# AD9864.net
KiCad netlist of a schematic drawn in Altium Designer
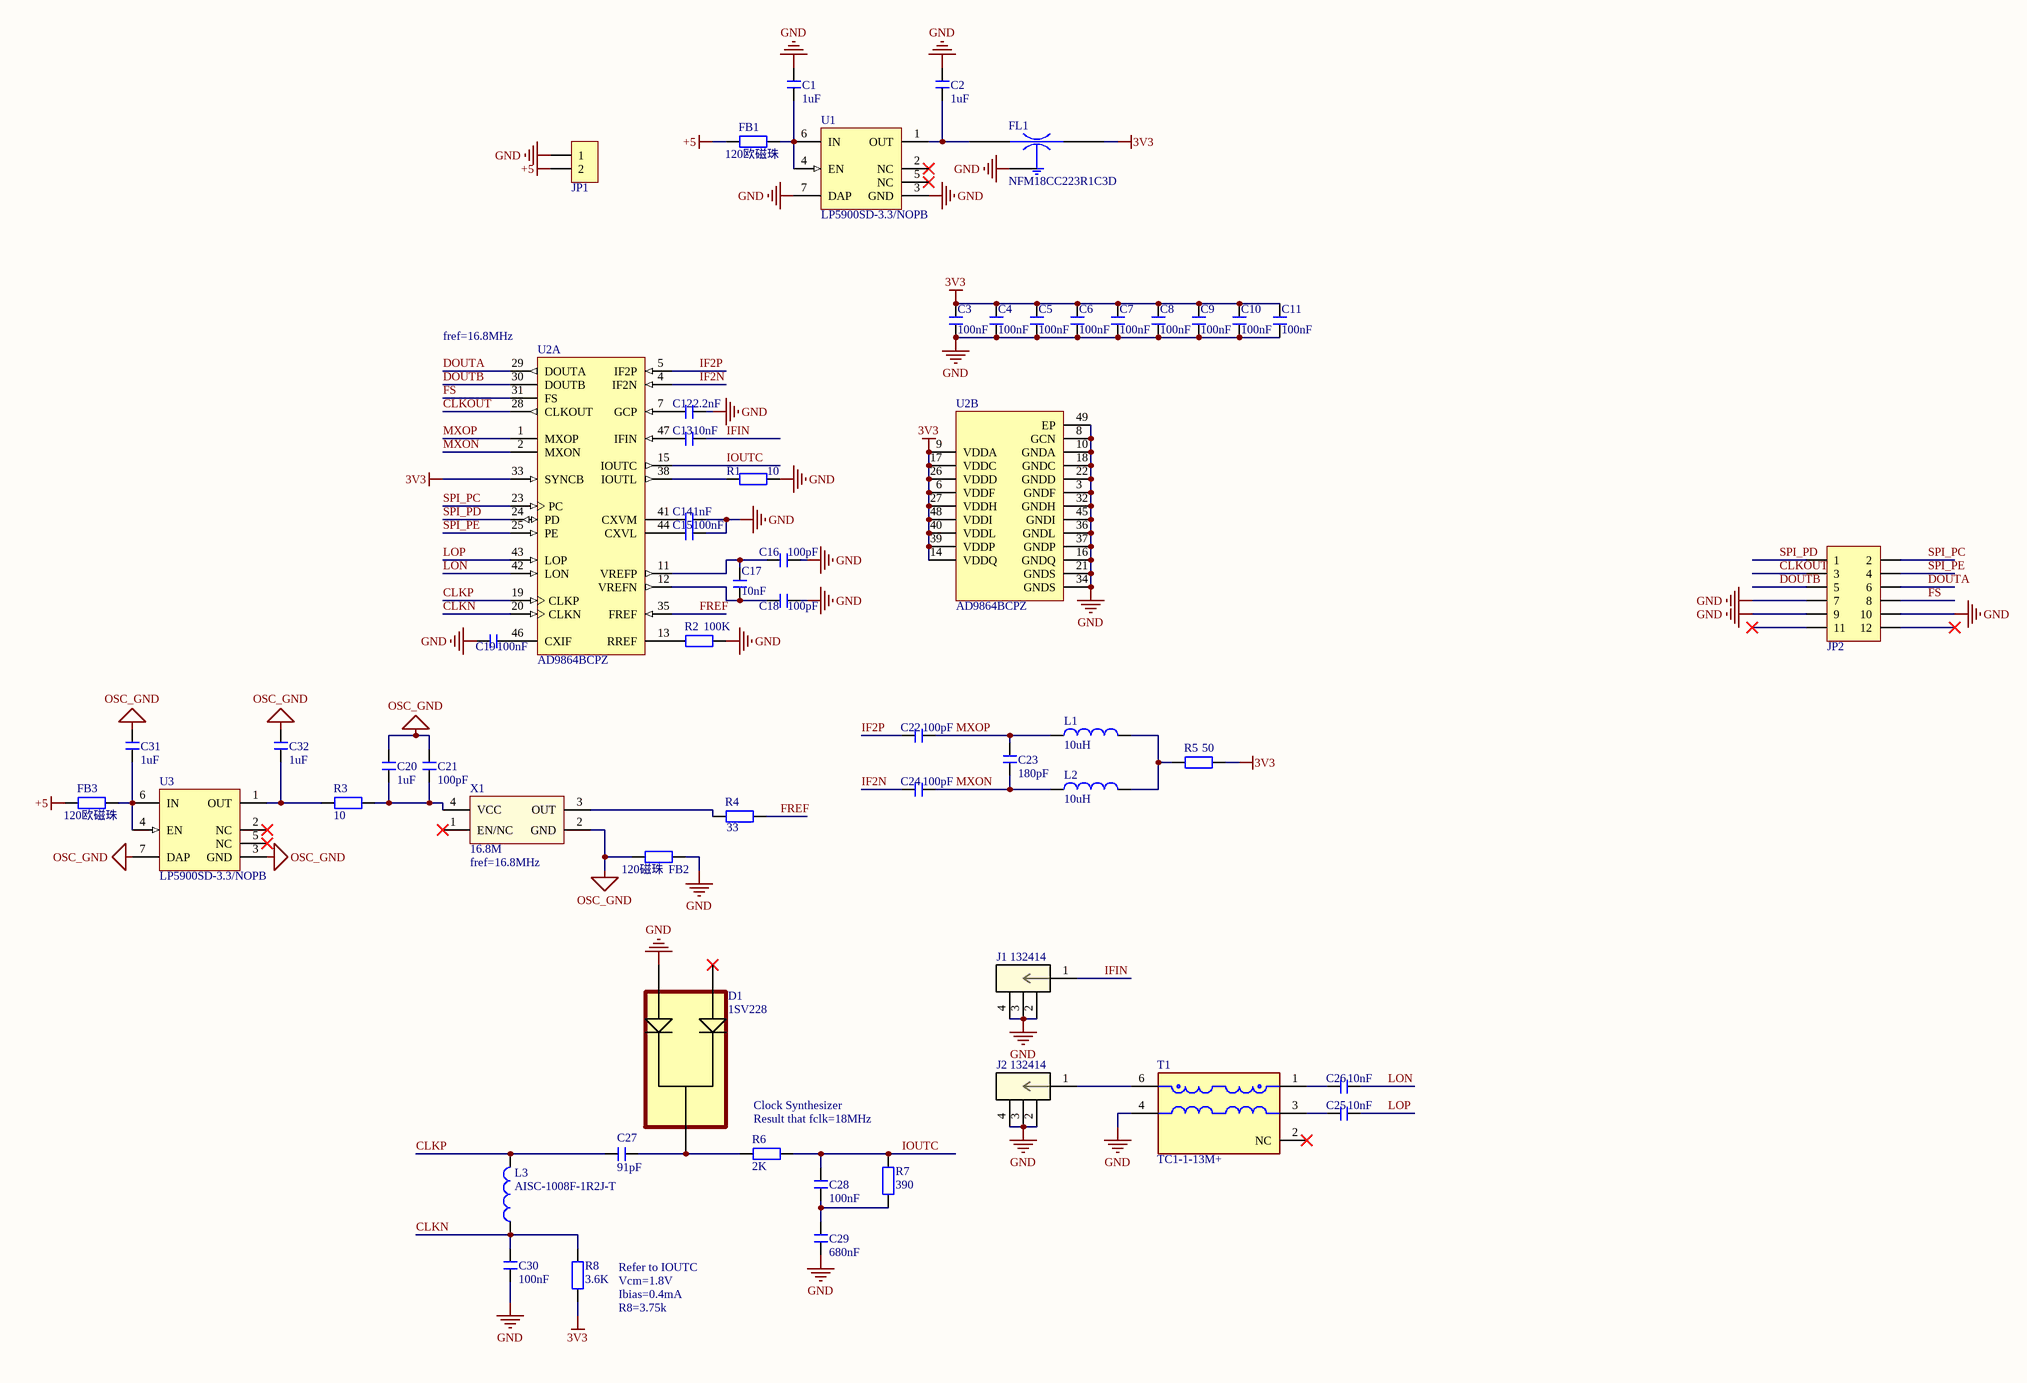
[diagram p0: AD9864.SchDoc]

(export (version "E")
  (design (tool "Eeschema 10.0.6"))
  (components
    (comp (ref "C1")
      (value "1uF")
      (footprint "C 0603_L")
      (description "贴片电容")
      (libsource (lib "01 - 电容-电阻-电感") (part "C"))
    )
    (comp (ref "C2")
      (value "1uF")
      (footprint "C 0603_L")
      (description "贴片电容")
      (libsource (lib "01 - 电容-电阻-电感") (part "C"))
    )
    (comp (ref "C3")
      (value "100nF")
      (footprint "C 0402_L")
      (description "贴片电容")
      (libsource (lib "01 - 电容-电阻-电感") (part "C"))
    )
    (comp (ref "C4")
      (value "100nF")
      (footprint "C 0402_L")
      (description "贴片电容")
      (libsource (lib "01 - 电容-电阻-电感") (part "C"))
    )
    (comp (ref "C5")
      (value "100nF")
      (footprint "C 0402_L")
      (description "贴片电容")
      (libsource (lib "01 - 电容-电阻-电感") (part "C"))
    )
    (comp (ref "C6")
      (value "100nF")
      (footprint "C 0402_L")
      (description "贴片电容")
      (libsource (lib "01 - 电容-电阻-电感") (part "C"))
    )
    (comp (ref "C7")
      (value "100nF")
      (footprint "C 0402_L")
      (description "贴片电容")
      (libsource (lib "01 - 电容-电阻-电感") (part "C"))
    )
    (comp (ref "C8")
      (value "100nF")
      (footprint "C 0402_L")
      (description "贴片电容")
      (libsource (lib "01 - 电容-电阻-电感") (part "C"))
    )
    (comp (ref "C9")
      (value "100nF")
      (footprint "C 0402_L")
      (description "贴片电容")
      (libsource (lib "01 - 电容-电阻-电感") (part "C"))
    )
    (comp (ref "C10")
      (value "100nF")
      (footprint "C 0402_L")
      (description "贴片电容")
      (libsource (lib "01 - 电容-电阻-电感") (part "C"))
    )
    (comp (ref "C11")
      (value "100nF")
      (footprint "C 0402_L")
      (description "贴片电容")
      (libsource (lib "01 - 电容-电阻-电感") (part "C"))
    )
    (comp (ref "C12")
      (value "2.2nF")
      (footprint "C 0402_L")
      (description "贴片电容")
      (libsource (lib "01 - 电容-电阻-电感") (part "C"))
    )
    (comp (ref "C13")
      (value "10nF")
      (footprint "C 0402_L")
      (description "贴片电容")
      (libsource (lib "01 - 电容-电阻-电感") (part "C"))
    )
    (comp (ref "C14")
      (value "1nF")
      (footprint "C 0402_L")
      (description "贴片电容")
      (libsource (lib "01 - 电容-电阻-电感") (part "C"))
    )
    (comp (ref "C15")
      (value "100nF")
      (footprint "C 0402_L")
      (description "贴片电容")
      (libsource (lib "01 - 电容-电阻-电感") (part "C"))
    )
    (comp (ref "C16")
      (value "100pF")
      (footprint "C 0402_L")
      (description "贴片电容")
      (libsource (lib "01 - 电容-电阻-电感") (part "C"))
    )
    (comp (ref "C17")
      (value "10nF")
      (footprint "C 0402_L")
      (description "贴片电容")
      (libsource (lib "01 - 电容-电阻-电感") (part "C"))
    )
    (comp (ref "C18")
      (value "100pF")
      (footprint "C 0402_L")
      (description "贴片电容")
      (libsource (lib "01 - 电容-电阻-电感") (part "C"))
    )
    (comp (ref "C19")
      (value "100nF")
      (footprint "C 0402_L")
      (description "贴片电容")
      (libsource (lib "01 - 电容-电阻-电感") (part "C"))
    )
    (comp (ref "C20")
      (value "1uF")
      (footprint "C 0603_L")
      (description "贴片电容")
      (libsource (lib "01 - 电容-电阻-电感") (part "C"))
    )
    (comp (ref "C21")
      (value "100pF")
      (footprint "C 0603_L")
      (description "贴片电容")
      (libsource (lib "01 - 电容-电阻-电感") (part "C"))
    )
    (comp (ref "C22")
      (value "100pF")
      (footprint "C 0402_L")
      (description "贴片电容")
      (libsource (lib "01 - 电容-电阻-电感") (part "C"))
    )
    (comp (ref "C23")
      (value "180pF")
      (footprint "C 0402_L")
      (description "贴片电容")
      (libsource (lib "01 - 电容-电阻-电感") (part "C"))
    )
    (comp (ref "C24")
      (value "100pF")
      (footprint "C 0402_L")
      (description "贴片电容")
      (libsource (lib "01 - 电容-电阻-电感") (part "C"))
    )
    (comp (ref "C25")
      (value "10nF")
      (footprint "C 0402_L")
      (description "贴片电容")
      (libsource (lib "01 - 电容-电阻-电感") (part "C"))
    )
    (comp (ref "C26")
      (value "10nF")
      (footprint "C 0402_L")
      (description "贴片电容")
      (libsource (lib "01 - 电容-电阻-电感") (part "C"))
    )
    (comp (ref "C27")
      (value "91pF")
      (footprint "C 0402_L")
      (description "贴片电容")
      (libsource (lib "01 - 电容-电阻-电感") (part "C"))
    )
    (comp (ref "C28")
      (value "100nF")
      (footprint "C 0402_L")
      (description "贴片电容")
      (libsource (lib "01 - 电容-电阻-电感") (part "C"))
    )
    (comp (ref "C29")
      (value "680nF")
      (footprint "C 0402_L")
      (description "贴片电容")
      (libsource (lib "01 - 电容-电阻-电感") (part "C"))
    )
    (comp (ref "C30")
      (value "100nF")
      (footprint "C 0402_L")
      (description "贴片电容")
      (libsource (lib "01 - 电容-电阻-电感") (part "C"))
    )
    (comp (ref "C31")
      (value "1uF")
      (footprint "C 0603_L")
      (description "贴片电容")
      (libsource (lib "01 - 电容-电阻-电感") (part "C"))
    )
    (comp (ref "C32")
      (value "1uF")
      (footprint "C 0603_L")
      (description "贴片电容")
      (libsource (lib "01 - 电容-电阻-电感") (part "C"))
    )
    (comp (ref "D1")
      (value "1SV228")
      (footprint "TRANS_SSM3J325F,LF")
      (description "Varactor 1 Pair Common Cathode 15V Surface Mount S-Mini")
      (fields (field (name "MF") "Toshiba"))
      (libsource (lib "1SV228") (part "1SV228"))
    )
    (comp (ref "FB1")
      (value "120欧磁珠")
      (footprint "R 0603_L")
      (description "贴片电阻")
      (libsource (lib "01 - 电容-电阻-电感") (part "R"))
    )
    (comp (ref "FB2")
      (value "120磁珠")
      (footprint "R 0603_L")
      (description "贴片电阻")
      (libsource (lib "01 - 电容-电阻-电感") (part "R"))
    )
    (comp (ref "FB3")
      (value "120欧磁珠")
      (footprint "R 0603_L")
      (description "贴片电阻")
      (libsource (lib "01 - 电容-电阻-电感") (part "R"))
    )
    (comp (ref "FL1")
      (value "NFM18CC223R1C3D")
      (footprint "FIL_NFM18CC223R1C3D")
      (description "SMD Capacitor with Capacitance: 22000pF Tol. 20%. Rated Voltage: 16Vdc")
      (fields (field (name "MF") "Murata"))
      (libsource (lib "NFM18CC223R1C3D") (part "NFM18CC223R1C3D"))
    )
    (comp (ref "J1")
      (value "132414")
      (footprint "CONN_132414_AMP")
      (description "No Description Available")
      (fields (field (name "COPYRIGHT") "Copyright (C) 2022 Ultra Librarian. All rights reserved."))
      (libsource (lib "细针大偏脚SMA(用这个)") (part "132414"))
    )
    (comp (ref "J2")
      (value "132414")
      (footprint "CONN_132414_AMP")
      (description "No Description Available")
      (fields (field (name "COPYRIGHT") "Copyright (C) 2022 Ultra Librarian. All rights reserved."))
      (libsource (lib "细针大偏脚SMA(用这个)") (part "132414"))
    )
    (comp (ref "JP1")
      (value "HDR-1X2")
      (footprint "KF2510-LI-2P")
      (description "2P接插件")
      (libsource (lib "18 - 接插件-脚距2.54mm (100mil) ") (part "Header 2"))
    )
    (comp (ref "JP2")
      (value "Header 6X2")
      (footprint "HDR2.54-WI-2x6P")
      (description "6*2P接插件")
      (libsource (lib "18 - 接插件-脚距2.54mm (100mil) ") (part "Header  6X2"))
    )
    (comp (ref "L1")
      (value "10uH")
      (footprint "L 0603")
      (description "小功率贴片电感")
      (libsource (lib "01 - 电容-电阻-电感") (part "L"))
    )
    (comp (ref "L2")
      (value "10uH")
      (footprint "L 0603")
      (description "小功率贴片电感")
      (libsource (lib "01 - 电容-电阻-电感") (part "L"))
    )
    (comp (ref "L3")
      (value "AISC-1008F-1R2J-T")
      (footprint "IND-SMD_L2.9-W2.8")
      (description "小功率贴片电感")
      (libsource (lib "01 - 电容-电阻-电感") (part "L"))
    )
    (comp (ref "R1")
      (value "10")
      (footprint "R 0402_L")
      (description "贴片电阻")
      (libsource (lib "01 - 电容-电阻-电感") (part "R"))
    )
    (comp (ref "R2")
      (value "100K")
      (footprint "R 0402_L")
      (description "贴片电阻")
      (libsource (lib "01 - 电容-电阻-电感") (part "R"))
    )
    (comp (ref "R3")
      (value "10")
      (footprint "R 0603_L")
      (description "贴片电阻")
      (libsource (lib "01 - 电容-电阻-电感") (part "R"))
    )
    (comp (ref "R4")
      (value "33")
      (footprint "R 0603_L")
      (description "贴片电阻")
      (libsource (lib "01 - 电容-电阻-电感") (part "R"))
    )
    (comp (ref "R5")
      (value "50")
      (footprint "R 0402_L")
      (description "贴片电阻")
      (libsource (lib "01 - 电容-电阻-电感") (part "R"))
    )
    (comp (ref "R6")
      (value "2K")
      (footprint "R 0402_L")
      (description "贴片电阻")
      (libsource (lib "01 - 电容-电阻-电感") (part "R"))
    )
    (comp (ref "R7")
      (value "390")
      (footprint "R 0402_L")
      (description "贴片电阻")
      (libsource (lib "01 - 电容-电阻-电感") (part "R"))
    )
    (comp (ref "R8")
      (value "3.6K")
      (footprint "R 0603_L")
      (description "贴片电阻")
      (libsource (lib "01 - 电容-电阻-电感") (part "R"))
    )
    (comp (ref "T1")
      (value "TC1-1-13M+")
      (footprint "FP-TC1-1-13M+-MFG")
      (description "RF Transformer 1: 1 5 Terminal SMD")
      (libsource (lib "DigiPCBA Workspace") (part "bfcd2037c1656edfb93934ecf7289be"))
    )
    (comp (ref "U1")
      (value "LP5900SD-3.3/NOPB")
      (footprint "NGF0006A_V")
      (description "150-mA, low-noise, low-IQ, low-dropout voltage regulator with enable 6-WSON -40 to 125")
      (libsource (lib "DigiPCBA Workspace") (part "PM-REG-LP5900-IL7"))
    )
    (comp (ref "U2")
      (value "AD9864BCPZ")
      (footprint "CP-48-1_M")
      (description "IC IF SUBSYSTEM GEN-PURP 48LFCSP")
      (libsource (lib "DigiPCBA Workspace") (part "ADI-AD9864-CP-48-1"))
    )
    (comp (ref "U3")
      (value "LP5900SD-3.3/NOPB")
      (footprint "NGF0006A_V")
      (description "150-mA, low-noise, low-IQ, low-dropout voltage regulator with enable 6-WSON -40 to 125")
      (libsource (lib "DigiPCBA Workspace") (part "PM-REG-LP5900-IL7"))
    )
    (comp (ref "X1")
      (value "16.8M")
      (footprint "OSC 3225-4P")
      (description "4脚有源晶振")
      (libsource (lib "03 - 按键-开关-晶振-蜂鸣器") (part "XTAL-ACT-4P"))
    )
  )
  (nets
    (net (code "1") (name "+5") (class "Default")
      (node (ref "FB1") (pin "1") (pinfunction "1_1") (pintype "passive"))
      (node (ref "FB3") (pin "1") (pinfunction "1_1") (pintype "passive"))
      (node (ref "JP1") (pin "2") (pinfunction "2_2") (pintype "passive"))
    )
    (net (code "2") (name "/CLKN") (class "Default")
      (node (ref "C30") (pin "2") (pinfunction "2_2") (pintype "passive"))
      (node (ref "L3") (pin "1") (pinfunction "1_1") (pintype "passive"))
      (node (ref "R8") (pin "2") (pinfunction "2_2") (pintype "passive"))
      (node (ref "U2") (pin "20") (pinfunction "CLKN_20") (pintype "input"))
    )
    (net (code "3") (name "/CLKOUT") (class "Default")
      (node (ref "JP2") (pin "3") (pinfunction "3_3") (pintype "passive"))
      (node (ref "U2") (pin "28") (pinfunction "CLKOUT_28") (pintype "output"))
    )
    (net (code "4") (name "/CLKP") (class "Default")
      (node (ref "C27") (pin "2") (pinfunction "2_2") (pintype "passive"))
      (node (ref "L3") (pin "2") (pinfunction "2_2") (pintype "passive"))
      (node (ref "U2") (pin "19") (pinfunction "CLKP_19") (pintype "input"))
    )
    (net (code "5") (name "/DOUTA") (class "Default")
      (node (ref "JP2") (pin "6") (pinfunction "6_6") (pintype "passive"))
      (node (ref "U2") (pin "29") (pinfunction "DOUTA_29") (pintype "output"))
    )
    (net (code "6") (name "/DOUTB") (class "Default")
      (node (ref "JP2") (pin "5") (pinfunction "5_5") (pintype "passive"))
      (node (ref "U2") (pin "30") (pinfunction "DOUTB_30") (pintype "tri_state"))
    )
    (net (code "7") (name "/FREF") (class "Default")
      (node (ref "R4") (pin "2") (pinfunction "2_2") (pintype "passive"))
      (node (ref "U2") (pin "35") (pinfunction "FREF_35") (pintype "input"))
    )
    (net (code "8") (name "/FS") (class "Default")
      (node (ref "JP2") (pin "8") (pinfunction "8_8") (pintype "passive"))
      (node (ref "U2") (pin "31") (pinfunction "FS_31") (pintype "tri_state"))
    )
    (net (code "9") (name "/IF2N") (class "Default")
      (node (ref "C24") (pin "1") (pinfunction "1_1") (pintype "passive"))
      (node (ref "U2") (pin "4") (pinfunction "IF2N_4") (pintype "input"))
    )
    (net (code "10") (name "/IF2P") (class "Default")
      (node (ref "C22") (pin "1") (pinfunction "1_1") (pintype "passive"))
      (node (ref "U2") (pin "5") (pinfunction "IF2P_5") (pintype "input"))
    )
    (net (code "11") (name "/IFIN") (class "Default")
      (node (ref "C13") (pin "2") (pinfunction "2_2") (pintype "passive"))
      (node (ref "J1") (pin "1") (pinfunction "1_1") (pintype "passive"))
    )
    (net (code "12") (name "/IOUTC") (class "Default")
      (node (ref "C28") (pin "2") (pinfunction "2_2") (pintype "passive"))
      (node (ref "R6") (pin "1") (pinfunction "1_1") (pintype "passive"))
      (node (ref "R7") (pin "1") (pinfunction "1_1") (pintype "passive"))
      (node (ref "U2") (pin "15") (pinfunction "IOUTC_15") (pintype "output"))
    )
    (net (code "13") (name "/LON") (class "Default")
      (node (ref "C26") (pin "2") (pinfunction "2_2") (pintype "passive"))
      (node (ref "U2") (pin "42") (pinfunction "LON_42") (pintype "input"))
    )
    (net (code "14") (name "/LOP") (class "Default")
      (node (ref "C25") (pin "2") (pinfunction "2_2") (pintype "passive"))
      (node (ref "U2") (pin "43") (pinfunction "LOP_43") (pintype "input"))
    )
    (net (code "15") (name "/MXON") (class "Default")
      (node (ref "C23") (pin "1") (pinfunction "1_1") (pintype "passive"))
      (node (ref "C24") (pin "2") (pinfunction "2_2") (pintype "passive"))
      (node (ref "L2") (pin "1") (pinfunction "1_1") (pintype "passive"))
      (node (ref "U2") (pin "2") (pinfunction "MXON_2") (pintype "open_collector"))
    )
    (net (code "16") (name "/MXOP") (class "Default")
      (node (ref "C22") (pin "2") (pinfunction "2_2") (pintype "passive"))
      (node (ref "C23") (pin "2") (pinfunction "2_2") (pintype "passive"))
      (node (ref "L1") (pin "1") (pinfunction "1_1") (pintype "passive"))
      (node (ref "U2") (pin "1") (pinfunction "MXOP_1") (pintype "open_collector"))
    )
    (net (code "17") (name "/SPI_PC") (class "Default")
      (node (ref "JP2") (pin "2") (pinfunction "2_2") (pintype "passive"))
      (node (ref "U2") (pin "23") (pinfunction "PC_23") (pintype "input"))
    )
    (net (code "18") (name "/SPI_PD") (class "Default")
      (node (ref "JP2") (pin "1") (pinfunction "1_1") (pintype "passive"))
      (node (ref "U2") (pin "24") (pinfunction "PD_24") (pintype "bidirectional"))
    )
    (net (code "19") (name "/SPI_PE") (class "Default")
      (node (ref "JP2") (pin "4") (pinfunction "4_4") (pintype "passive"))
      (node (ref "U2") (pin "25") (pinfunction "PE_25") (pintype "input"))
    )
    (net (code "20") (name "3V3") (class "Default")
      (node (ref "C10") (pin "2") (pinfunction "2_2") (pintype "passive"))
      (node (ref "C11") (pin "2") (pinfunction "2_2") (pintype "passive"))
      (node (ref "C3") (pin "2") (pinfunction "2_2") (pintype "passive"))
      (node (ref "C4") (pin "2") (pinfunction "2_2") (pintype "passive"))
      (node (ref "C5") (pin "2") (pinfunction "2_2") (pintype "passive"))
      (node (ref "C6") (pin "2") (pinfunction "2_2") (pintype "passive"))
      (node (ref "C7") (pin "2") (pinfunction "2_2") (pintype "passive"))
      (node (ref "C8") (pin "2") (pinfunction "2_2") (pintype "passive"))
      (node (ref "C9") (pin "2") (pinfunction "2_2") (pintype "passive"))
      (node (ref "FL1") (pin "3") (pintype "passive"))
      (node (ref "R5") (pin "2") (pinfunction "2_2") (pintype "passive"))
      (node (ref "R8") (pin "1") (pinfunction "1_1") (pintype "passive"))
      (node (ref "U2") (pin "14") (pinfunction "VDDQ_14") (pintype "power_in"))
      (node (ref "U2") (pin "17") (pinfunction "VDDC_17") (pintype "power_in"))
      (node (ref "U2") (pin "26") (pinfunction "VDDD_26") (pintype "power_in"))
      (node (ref "U2") (pin "27") (pinfunction "VDDH_27") (pintype "power_in"))
      (node (ref "U2") (pin "33") (pinfunction "SYNCB_33") (pintype "input"))
      (node (ref "U2") (pin "39") (pinfunction "VDDP_39") (pintype "power_in"))
      (node (ref "U2") (pin "40") (pinfunction "VDDL_40") (pintype "power_in"))
      (node (ref "U2") (pin "48") (pinfunction "VDDI_48") (pintype "power_in"))
      (node (ref "U2") (pin "6") (pinfunction "VDDF_6") (pintype "power_in"))
      (node (ref "U2") (pin "9") (pinfunction "VDDA_9") (pintype "power_in"))
    )
    (net (code "21") (name "GND") (class "Default")
      (node (ref "C1") (pin "2") (pinfunction "2_2") (pintype "passive"))
      (node (ref "C10") (pin "1") (pinfunction "1_1") (pintype "passive"))
      (node (ref "C11") (pin "1") (pinfunction "1_1") (pintype "passive"))
      (node (ref "C12") (pin "2") (pinfunction "2_2") (pintype "passive"))
      (node (ref "C14") (pin "1") (pinfunction "1_1") (pintype "passive"))
      (node (ref "C15") (pin "1") (pinfunction "1_1") (pintype "passive"))
      (node (ref "C16") (pin "2") (pinfunction "2_2") (pintype "passive"))
      (node (ref "C18") (pin "2") (pinfunction "2_2") (pintype "passive"))
      (node (ref "C19") (pin "1") (pinfunction "1_1") (pintype "passive"))
      (node (ref "C2") (pin "2") (pinfunction "2_2") (pintype "passive"))
      (node (ref "C29") (pin "1") (pinfunction "1_1") (pintype "passive"))
      (node (ref "C3") (pin "1") (pinfunction "1_1") (pintype "passive"))
      (node (ref "C30") (pin "1") (pinfunction "1_1") (pintype "passive"))
      (node (ref "C4") (pin "1") (pinfunction "1_1") (pintype "passive"))
      (node (ref "C5") (pin "1") (pinfunction "1_1") (pintype "passive"))
      (node (ref "C6") (pin "1") (pinfunction "1_1") (pintype "passive"))
      (node (ref "C7") (pin "1") (pinfunction "1_1") (pintype "passive"))
      (node (ref "C8") (pin "1") (pinfunction "1_1") (pintype "passive"))
      (node (ref "C9") (pin "1") (pinfunction "1_1") (pintype "passive"))
      (node (ref "D1") (pin "2") (pinfunction "2_2") (pintype "passive"))
      (node (ref "FB2") (pin "2") (pinfunction "2_2") (pintype "passive"))
      (node (ref "FL1") (pin "2") (pinfunction "GND_2") (pintype "power_in"))
      (node (ref "J1") (pin "2") (pinfunction "2_2") (pintype "passive"))
      (node (ref "J1") (pin "3") (pinfunction "3_3") (pintype "passive"))
      (node (ref "J1") (pin "4") (pinfunction "4_4") (pintype "passive"))
      (node (ref "J2") (pin "2") (pinfunction "2_2") (pintype "passive"))
      (node (ref "J2") (pin "3") (pinfunction "3_3") (pintype "passive"))
      (node (ref "J2") (pin "4") (pinfunction "4_4") (pintype "passive"))
      (node (ref "JP1") (pin "1") (pinfunction "1_1") (pintype "passive"))
      (node (ref "JP2") (pin "10") (pinfunction "10_10") (pintype "passive"))
      (node (ref "JP2") (pin "7") (pinfunction "7_7") (pintype "passive"))
      (node (ref "JP2") (pin "9") (pinfunction "9_9") (pintype "passive"))
      (node (ref "R1") (pin "2") (pinfunction "2_2") (pintype "passive"))
      (node (ref "R2") (pin "2") (pinfunction "2_2") (pintype "passive"))
      (node (ref "T1") (pin "4") (pinfunction "PRIMARY_4") (pintype "passive"))
      (node (ref "U1") (pin "3") (pinfunction "GND_3") (pintype "power_in"))
      (node (ref "U1") (pin "7") (pinfunction "DAP_7") (pintype "power_in"))
      (node (ref "U2") (pin "10") (pinfunction "GNDA_10") (pintype "power_in"))
      (node (ref "U2") (pin "16") (pinfunction "GNDQ_16") (pintype "power_in"))
      (node (ref "U2") (pin "18") (pinfunction "GNDC_18") (pintype "power_in"))
      (node (ref "U2") (pin "21") (pinfunction "GNDS_21") (pintype "power_in"))
      (node (ref "U2") (pin "22") (pinfunction "GNDD_22") (pintype "power_in"))
      (node (ref "U2") (pin "3") (pinfunction "GNDF_3") (pintype "power_in"))
      (node (ref "U2") (pin "32") (pinfunction "GNDH_32") (pintype "power_in"))
      (node (ref "U2") (pin "34") (pinfunction "GNDS_34") (pintype "power_in"))
      (node (ref "U2") (pin "36") (pinfunction "GNDL_36") (pintype "power_in"))
      (node (ref "U2") (pin "37") (pinfunction "GNDP_37") (pintype "power_in"))
      (node (ref "U2") (pin "45") (pinfunction "GNDI_45") (pintype "power_in"))
      (node (ref "U2") (pin "49") (pinfunction "EP_49") (pintype "passive"))
      (node (ref "U2") (pin "8") (pinfunction "GCN_8") (pintype "power_in"))
    )
    (net (code "22") (name "Net-(C27-Pad1)") (class "Default")
      (node (ref "C27") (pin "1") (pinfunction "1_1") (pintype "passive"))
      (node (ref "D1") (pin "3") (pinfunction "3_3") (pintype "passive"))
      (node (ref "R6") (pin "2") (pinfunction "2_2") (pintype "passive"))
    )
    (net (code "23") (name "Net-(C28-Pad1)") (class "Default")
      (node (ref "C28") (pin "1") (pinfunction "1_1") (pintype "passive"))
      (node (ref "C29") (pin "2") (pinfunction "2_2") (pintype "passive"))
      (node (ref "R7") (pin "2") (pinfunction "2_2") (pintype "passive"))
    )
    (net (code "24") (name "Net-(L1-Pad2)") (class "Default")
      (node (ref "L1") (pin "2") (pinfunction "2_2") (pintype "passive"))
      (node (ref "L2") (pin "2") (pinfunction "2_2") (pintype "passive"))
      (node (ref "R5") (pin "1") (pinfunction "1_1") (pintype "passive"))
    )
    (net (code "25") (name "Net-(T1-PRIMARY_DOT)") (class "Default")
      (node (ref "J2") (pin "1") (pinfunction "1_1") (pintype "passive"))
      (node (ref "T1") (pin "6") (pinfunction "PRIMARY_DOT_6") (pintype "passive"))
    )
    (net (code "26") (name "Net-(T1-SECONDARY)") (class "Default")
      (node (ref "C25") (pin "1") (pinfunction "1_1") (pintype "passive"))
      (node (ref "T1") (pin "3") (pinfunction "SECONDARY_3") (pintype "passive"))
    )
    (net (code "27") (name "Net-(T1-SECONDARY_DOT)") (class "Default")
      (node (ref "C26") (pin "1") (pinfunction "1_1") (pintype "passive"))
      (node (ref "T1") (pin "1") (pinfunction "SECONDARY_DOT_1") (pintype "passive"))
    )
    (net (code "28") (name "Net-(U1-EN)") (class "Default")
      (node (ref "C1") (pin "1") (pinfunction "1_1") (pintype "passive"))
      (node (ref "FB1") (pin "2") (pinfunction "2_2") (pintype "passive"))
      (node (ref "U1") (pin "4") (pinfunction "EN_4") (pintype "input"))
      (node (ref "U1") (pin "6") (pinfunction "IN_6") (pintype "power_in"))
    )
    (net (code "29") (name "Net-(U1-OUT)") (class "Default")
      (node (ref "C2") (pin "1") (pinfunction "1_1") (pintype "passive"))
      (node (ref "FL1") (pin "1") (pintype "passive"))
      (node (ref "U1") (pin "1") (pinfunction "OUT_1") (pintype "power_in"))
    )
    (net (code "30") (name "Net-(U2A-CXIF)") (class "Default")
      (node (ref "C19") (pin "2") (pinfunction "2_2") (pintype "passive"))
      (node (ref "U2") (pin "46") (pinfunction "CXIF_46") (pintype "passive"))
    )
    (net (code "31") (name "Net-(U2A-CXVL)") (class "Default")
      (node (ref "C15") (pin "2") (pinfunction "2_2") (pintype "passive"))
      (node (ref "U2") (pin "44") (pinfunction "CXVL_44") (pintype "passive"))
    )
    (net (code "32") (name "Net-(U2A-CXVM)") (class "Default")
      (node (ref "C14") (pin "2") (pinfunction "2_2") (pintype "passive"))
      (node (ref "U2") (pin "41") (pinfunction "CXVM_41") (pintype "passive"))
    )
    (net (code "33") (name "Net-(U2A-GCP)") (class "Default")
      (node (ref "C12") (pin "1") (pinfunction "1_1") (pintype "passive"))
      (node (ref "U2") (pin "7") (pinfunction "GCP_7") (pintype "input"))
    )
    (net (code "34") (name "Net-(U2A-IFIN)") (class "Default")
      (node (ref "C13") (pin "1") (pinfunction "1_1") (pintype "passive"))
      (node (ref "U2") (pin "47") (pinfunction "IFIN_47") (pintype "input"))
    )
    (net (code "35") (name "Net-(U2A-IOUTL)") (class "Default")
      (node (ref "R1") (pin "1") (pinfunction "1_1") (pintype "passive"))
      (node (ref "U2") (pin "38") (pinfunction "IOUTL_38") (pintype "output"))
    )
    (net (code "36") (name "Net-(U2A-RREF)") (class "Default")
      (node (ref "R2") (pin "1") (pinfunction "1_1") (pintype "passive"))
      (node (ref "U2") (pin "13") (pinfunction "RREF_13") (pintype "passive"))
    )
    (net (code "37") (name "Net-(U2A-VREFN)") (class "Default")
      (node (ref "C17") (pin "1") (pinfunction "1_1") (pintype "passive"))
      (node (ref "C18") (pin "1") (pinfunction "1_1") (pintype "passive"))
      (node (ref "U2") (pin "12") (pinfunction "VREFN_12") (pintype "output"))
    )
    (net (code "38") (name "Net-(U2A-VREFP)") (class "Default")
      (node (ref "C16") (pin "1") (pinfunction "1_1") (pintype "passive"))
      (node (ref "C17") (pin "2") (pinfunction "2_2") (pintype "passive"))
      (node (ref "U2") (pin "11") (pinfunction "VREFP_11") (pintype "output"))
    )
    (net (code "39") (name "Net-(U3-EN)") (class "Default")
      (node (ref "C31") (pin "1") (pinfunction "1_1") (pintype "passive"))
      (node (ref "FB3") (pin "2") (pinfunction "2_2") (pintype "passive"))
      (node (ref "U3") (pin "4") (pinfunction "EN_4") (pintype "input"))
      (node (ref "U3") (pin "6") (pinfunction "IN_6") (pintype "power_in"))
    )
    (net (code "40") (name "Net-(U3-OUT)") (class "Default")
      (node (ref "C32") (pin "1") (pinfunction "1_1") (pintype "passive"))
      (node (ref "R3") (pin "1") (pinfunction "1_1") (pintype "passive"))
      (node (ref "U3") (pin "1") (pinfunction "OUT_1") (pintype "power_in"))
    )
    (net (code "41") (name "Net-(X1-OUT)") (class "Default")
      (node (ref "R4") (pin "1") (pinfunction "1_1") (pintype "passive"))
      (node (ref "X1") (pin "3") (pinfunction "OUT_3") (pintype "passive"))
    )
    (net (code "42") (name "Net-(X1-VCC)") (class "Default")
      (node (ref "C20") (pin "1") (pinfunction "1_1") (pintype "passive"))
      (node (ref "C21") (pin "1") (pinfunction "1_1") (pintype "passive"))
      (node (ref "R3") (pin "2") (pinfunction "2_2") (pintype "passive"))
      (node (ref "X1") (pin "4") (pinfunction "VCC_4") (pintype "passive"))
    )
    (net (code "43") (name "OSC_GND") (class "Default")
      (node (ref "C20") (pin "2") (pinfunction "2_2") (pintype "passive"))
      (node (ref "C21") (pin "2") (pinfunction "2_2") (pintype "passive"))
      (node (ref "C31") (pin "2") (pinfunction "2_2") (pintype "passive"))
      (node (ref "C32") (pin "2") (pinfunction "2_2") (pintype "passive"))
      (node (ref "FB2") (pin "1") (pinfunction "1_1") (pintype "passive"))
      (node (ref "U3") (pin "3") (pinfunction "GND_3") (pintype "power_in"))
      (node (ref "U3") (pin "7") (pinfunction "DAP_7") (pintype "power_in"))
      (node (ref "X1") (pin "2") (pinfunction "GND_2") (pintype "passive"))
    )
    (net (code "44") (name "unconnected-(D1-Pad1)") (class "Default")
      (node (ref "D1") (pin "1") (pinfunction "1_1") (pintype "passive+no_connect"))
    )
    (net (code "45") (name "unconnected-(JP2-Pad11)") (class "Default")
      (node (ref "JP2") (pin "11") (pinfunction "11_11") (pintype "passive+no_connect"))
    )
    (net (code "46") (name "unconnected-(JP2-Pad12)") (class "Default")
      (node (ref "JP2") (pin "12") (pinfunction "12_12") (pintype "passive+no_connect"))
    )
    (net (code "47") (name "unconnected-(T1-NC-Pad2)") (class "Default")
      (node (ref "T1") (pin "2") (pinfunction "NC_2") (pintype "passive+no_connect"))
    )
    (net (code "48") (name "unconnected-(U1-NC-Pad2)") (class "Default")
      (node (ref "U1") (pin "2") (pinfunction "NC_2") (pintype "passive+no_connect"))
    )
    (net (code "49") (name "unconnected-(U1-NC-Pad5)") (class "Default")
      (node (ref "U1") (pin "5") (pinfunction "NC_5") (pintype "passive+no_connect"))
    )
    (net (code "50") (name "unconnected-(U3-NC-Pad2)") (class "Default")
      (node (ref "U3") (pin "2") (pinfunction "NC_2") (pintype "passive+no_connect"))
    )
    (net (code "51") (name "unconnected-(U3-NC-Pad5)") (class "Default")
      (node (ref "U3") (pin "5") (pinfunction "NC_5") (pintype "passive+no_connect"))
    )
    (net (code "52") (name "unconnected-(X1-EN{slash}NC-Pad1)") (class "Default")
      (node (ref "X1") (pin "1") (pinfunction "EN/NC_1") (pintype "passive+no_connect"))
    )
  )
)
